# main.net
KiCad netlist of a schematic drawn in EAGLE
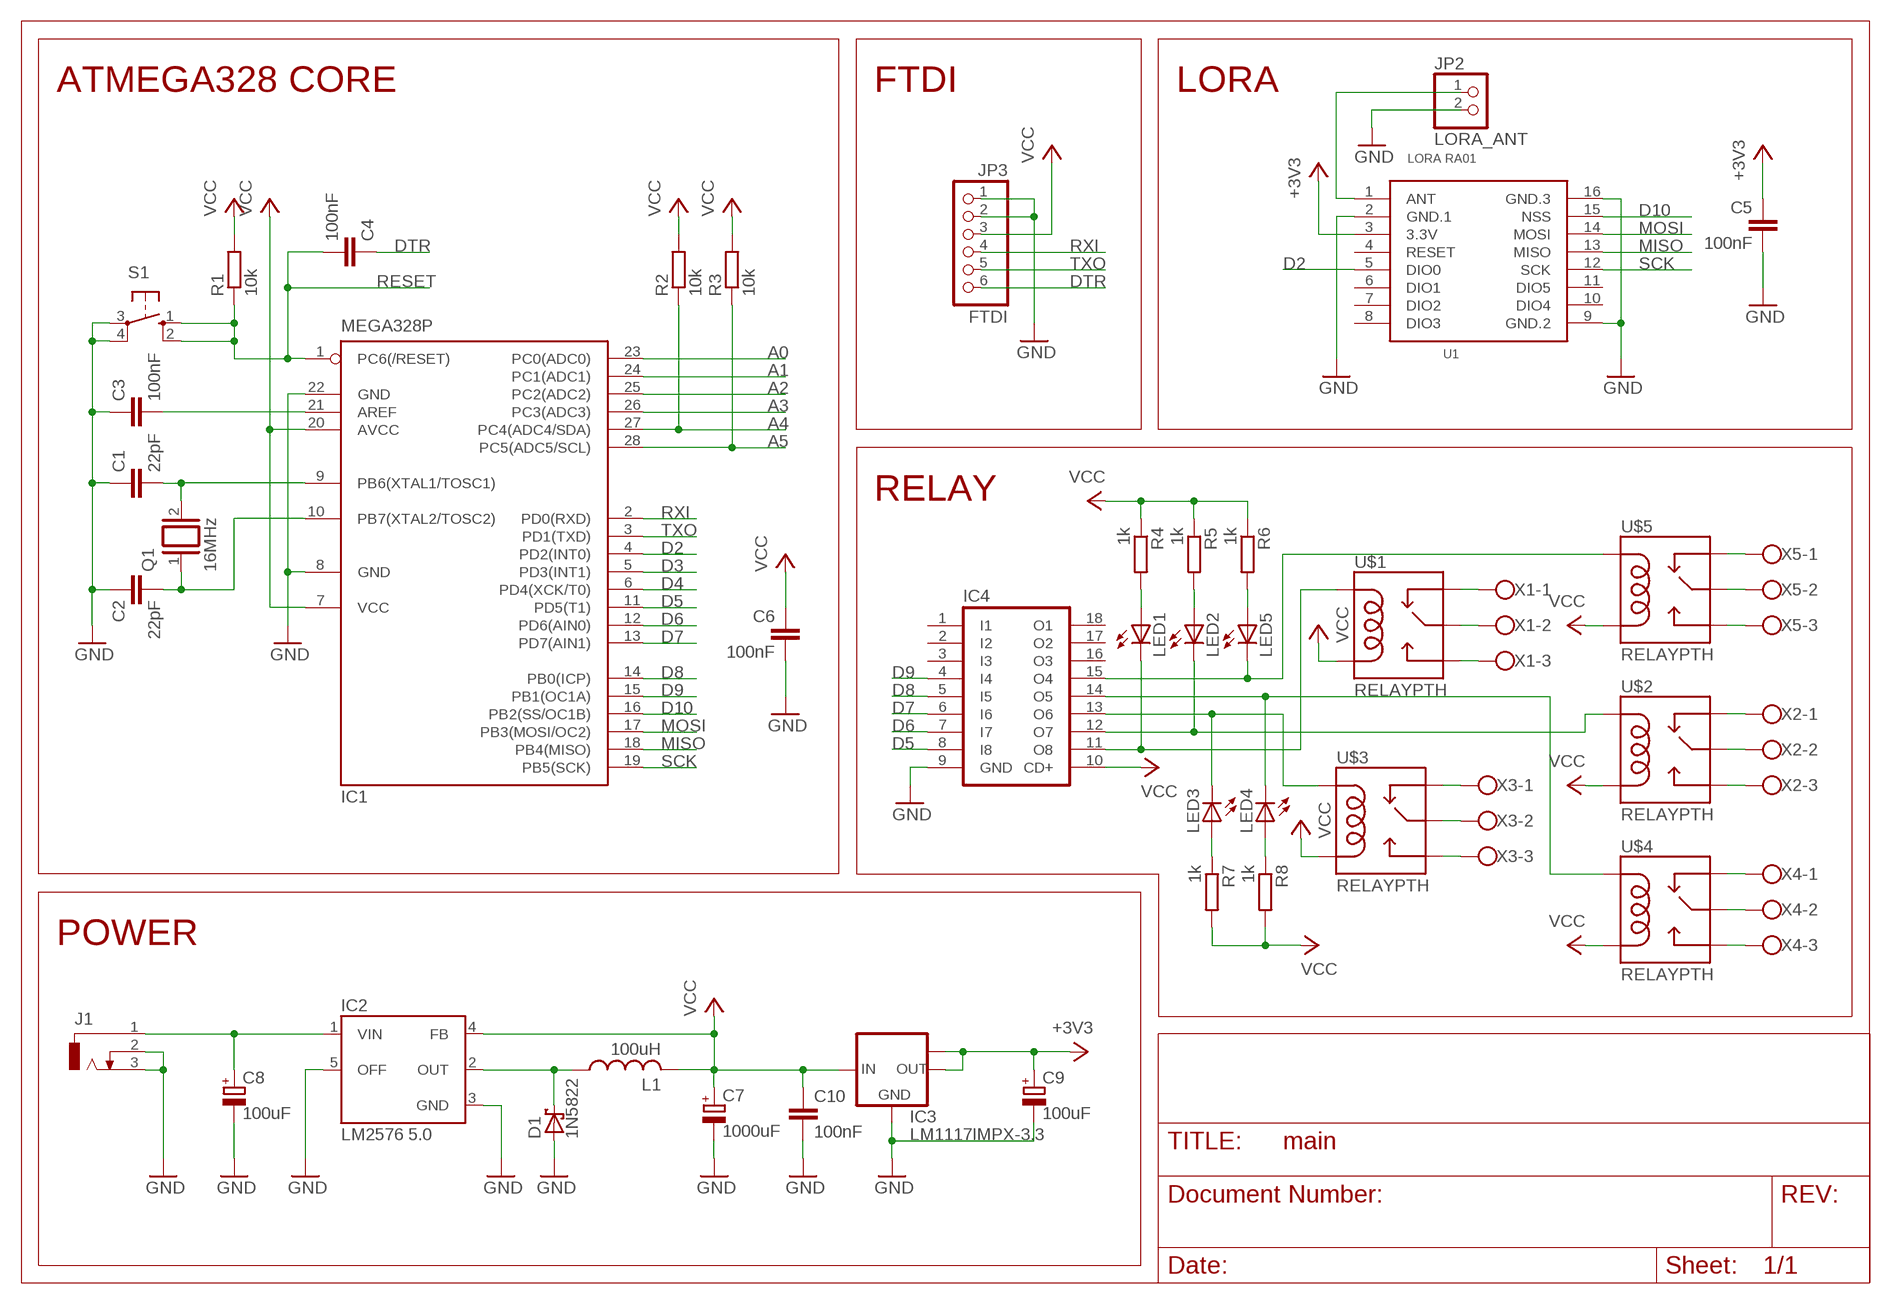
[diagram p0: schematic, sheet 1]

(export (version "E")
  (design (tool "Eeschema 10.0.6"))
  (components
    (comp (ref "C1")
      (value "22pF")
      (footprint "eagle-import:C050-024X044")
      (libsource (lib "eagle-import") (part "C-EU050-024X044"))
    )
    (comp (ref "C2")
      (value "22pF")
      (footprint "eagle-import:C050-024X044")
      (libsource (lib "eagle-import") (part "C-EU050-024X044"))
    )
    (comp (ref "C3")
      (value "100nF")
      (footprint "eagle-import:C050-024X044")
      (libsource (lib "eagle-import") (part "C-EU050-024X044"))
    )
    (comp (ref "C4")
      (value "100nF")
      (footprint "eagle-import:C050-024X044")
      (libsource (lib "eagle-import") (part "C-EU050-024X044"))
    )
    (comp (ref "C5")
      (value "100nF")
      (footprint "eagle-import:C050-024X044")
      (libsource (lib "eagle-import") (part "C-EU050-024X044"))
    )
    (comp (ref "C6")
      (value "100nF")
      (footprint "eagle-import:C050-024X044")
      (libsource (lib "eagle-import") (part "C-EU050-024X044"))
    )
    (comp (ref "C7")
      (value "1000uF")
      (footprint "eagle-import:E5-13")
      (libsource (lib "eagle-import") (part "CPOL-EUE5-13"))
    )
    (comp (ref "C8")
      (value "100uF")
      (footprint "eagle-import:E5-8,5")
      (libsource (lib "eagle-import") (part "CPOL-EUE5-8.5"))
    )
    (comp (ref "C9")
      (value "100uF")
      (footprint "eagle-import:E3,5-10")
      (libsource (lib "eagle-import") (part "CPOL-EUE3.5-10"))
    )
    (comp (ref "C10")
      (value "100nF")
      (footprint "eagle-import:C050-024X044")
      (libsource (lib "eagle-import") (part "C-EU050-024X044"))
    )
    (comp (ref "D1")
      (value "1N5822")
      (footprint "eagle-import:DO201T15")
      (libsource (lib "eagle-import") (part "SCHOTTKY-DIODEDO201T15"))
    )
    (comp (ref "IC1")
      (value "MEGA328P")
      (footprint "eagle-import:DIL28-3")
      (libsource (lib "eagle-import") (part "MEGA8-P"))
    )
    (comp (ref "IC2")
      (value "LM2576 5.0")
      (footprint "eagle-import:TO263-5")
      (libsource (lib "eagle-import") (part "LM2576S"))
    )
    (comp (ref "IC3")
      (value "LM1117IMPX-3.3")
      (footprint "eagle-import:SOT223")
      (libsource (lib "eagle-import") (part "LM1117IMPX-3.3"))
    )
    (comp (ref "IC4")
      (value "ULN2803A")
      (footprint "eagle-import:DIL18")
      (libsource (lib "eagle-import") (part "ULN2803A"))
    )
    (comp (ref "J1")
      (value "DCJ0303")
      (footprint "eagle-import:DCJ0303")
      (libsource (lib "eagle-import") (part "DCJ0303"))
    )
    (comp (ref "JP2")
      (value "LORA_ANT")
      (footprint "eagle-import:1X02")
      (libsource (lib "eagle-import") (part "PINHD-1X2"))
    )
    (comp (ref "JP3")
      (value "FTDI")
      (footprint "eagle-import:1X06")
      (libsource (lib "eagle-import") (part "PINHD-1X6"))
    )
    (comp (ref "L1")
      (value "100uH")
      (footprint "eagle-import:6000-XXXX-RC")
      (libsource (lib "eagle-import") (part "L-US6000-XXX-RC"))
    )
    (comp (ref "LED1")
      (value "LED3MM")
      (footprint "eagle-import:LED3MM")
      (libsource (lib "eagle-import") (part "LED3MM"))
    )
    (comp (ref "LED2")
      (value "LED3MM")
      (footprint "eagle-import:LED3MM")
      (libsource (lib "eagle-import") (part "LED3MM"))
    )
    (comp (ref "LED3")
      (value "LED3MM")
      (footprint "eagle-import:LED3MM")
      (libsource (lib "eagle-import") (part "LED3MM"))
    )
    (comp (ref "LED4")
      (value "LED3MM")
      (footprint "eagle-import:LED3MM")
      (libsource (lib "eagle-import") (part "LED3MM"))
    )
    (comp (ref "LED5")
      (value "LED3MM")
      (footprint "eagle-import:LED3MM")
      (libsource (lib "eagle-import") (part "LED3MM"))
    )
    (comp (ref "Q1")
      (value "16MHz")
      (footprint "eagle-import:QS")
      (libsource (lib "eagle-import") (part "XTAL/S"))
    )
    (comp (ref "R1")
      (value "10k")
      (footprint "eagle-import:0207_10")
      (libsource (lib "eagle-import") (part "R-EU_0207/10"))
    )
    (comp (ref "R2")
      (value "10k")
      (footprint "eagle-import:0207_10")
      (libsource (lib "eagle-import") (part "R-EU_0207/10"))
    )
    (comp (ref "R3")
      (value "10k")
      (footprint "eagle-import:0207_10")
      (libsource (lib "eagle-import") (part "R-EU_0207/10"))
    )
    (comp (ref "R4")
      (value "1k")
      (footprint "eagle-import:0207_10")
      (libsource (lib "eagle-import") (part "R-EU_0207/10"))
    )
    (comp (ref "R5")
      (value "1k")
      (footprint "eagle-import:0207_10")
      (libsource (lib "eagle-import") (part "R-EU_0207/10"))
    )
    (comp (ref "R6")
      (value "1k")
      (footprint "eagle-import:0207_10")
      (libsource (lib "eagle-import") (part "R-EU_0207/10"))
    )
    (comp (ref "R7")
      (value "1k")
      (footprint "eagle-import:0207_10")
      (libsource (lib "eagle-import") (part "R-EU_0207/10"))
    )
    (comp (ref "R8")
      (value "1k")
      (footprint "eagle-import:0207_10")
      (libsource (lib "eagle-import") (part "R-EU_0207/10"))
    )
    (comp (ref "S1")
      (value "10-XX")
      (footprint "eagle-import:B3F-10XX")
      (fields (field (name "MPN") "B3F-1000"))
      (libsource (lib "eagle-import") (part "10-XX"))
    )
    (comp (ref "U$1")
      (value "RELAYPTH")
      (footprint "eagle-import:SRD-05VDC-SL-C")
      (libsource (lib "eagle-import") (part "RELAYPTH"))
    )
    (comp (ref "U$2")
      (value "RELAYPTH")
      (footprint "eagle-import:SRD-05VDC-SL-C")
      (libsource (lib "eagle-import") (part "RELAYPTH"))
    )
    (comp (ref "U$3")
      (value "RELAYPTH")
      (footprint "eagle-import:SRD-05VDC-SL-C")
      (libsource (lib "eagle-import") (part "RELAYPTH"))
    )
    (comp (ref "U$4")
      (value "RELAYPTH")
      (footprint "eagle-import:SRD-05VDC-SL-C")
      (libsource (lib "eagle-import") (part "RELAYPTH"))
    )
    (comp (ref "U$5")
      (value "RELAYPTH")
      (footprint "eagle-import:SRD-05VDC-SL-C")
      (libsource (lib "eagle-import") (part "RELAYPTH"))
    )
    (comp (ref "U1")
      (value "LORA RA01")
      (footprint "eagle-import:LORA-RA1-SMD")
      (libsource (lib "eagle-import") (part "LORA-RA-01-433MHZ"))
    )
    (comp (ref "X1")
      (value "W237-103")
      (footprint "eagle-import:W237-103")
      (fields (field (name "MPN") "237-103"))
      (libsource (lib "eagle-import") (part "W237-103"))
    )
    (comp (ref "X2")
      (value "W237-103")
      (footprint "eagle-import:W237-103")
      (fields (field (name "MPN") "237-103"))
      (libsource (lib "eagle-import") (part "W237-103"))
    )
    (comp (ref "X3")
      (value "W237-103")
      (footprint "eagle-import:W237-103")
      (fields (field (name "MPN") "237-103"))
      (libsource (lib "eagle-import") (part "W237-103"))
    )
    (comp (ref "X4")
      (value "W237-103")
      (footprint "eagle-import:W237-103")
      (fields (field (name "MPN") "237-103"))
      (libsource (lib "eagle-import") (part "W237-103"))
    )
    (comp (ref "X5")
      (value "W237-103")
      (footprint "eagle-import:W237-103")
      (fields (field (name "MPN") "237-103"))
      (libsource (lib "eagle-import") (part "W237-103"))
    )
  )
  (nets
    (net (code "1") (name "+3V3") (class "Default")
      (node (ref "C5") (pin "1") (pinfunction "1_1") (pintype "passive"))
      (node (ref "C9") (pin "+") (pinfunction "+_+") (pintype "passive"))
      (node (ref "IC3") (pin "2") (pinfunction "OUT_2") (pintype "passive"))
      (node (ref "IC3") (pin "TAB") (pinfunction "OUT1_TAB") (pintype "passive"))
      (node (ref "U1") (pin "3") (pinfunction "3.3V_3") (pintype "power_in"))
    )
    (net (code "2") (name "/A0") (class "Default")
      (node (ref "IC1") (pin "23") (pinfunction "PC0(ADC0)_23") (pintype "bidirectional"))
    )
    (net (code "3") (name "/A1") (class "Default")
      (node (ref "IC1") (pin "24") (pinfunction "PC1(ADC1)_24") (pintype "bidirectional"))
    )
    (net (code "4") (name "/A2") (class "Default")
      (node (ref "IC1") (pin "25") (pinfunction "PC2(ADC2)_25") (pintype "bidirectional"))
    )
    (net (code "5") (name "/A3") (class "Default")
      (node (ref "IC1") (pin "26") (pinfunction "PC3(ADC3)_26") (pintype "bidirectional"))
    )
    (net (code "6") (name "/A4") (class "Default")
      (node (ref "IC1") (pin "27") (pinfunction "PC4(ADC4/SDA)_27") (pintype "bidirectional"))
      (node (ref "R2") (pin "1") (pinfunction "1_1") (pintype "passive"))
    )
    (net (code "7") (name "/A5") (class "Default")
      (node (ref "IC1") (pin "28") (pinfunction "PC5(ADC5/SCL)_28") (pintype "bidirectional"))
      (node (ref "R3") (pin "1") (pinfunction "1_1") (pintype "passive"))
    )
    (net (code "8") (name "/D2") (class "Default")
      (node (ref "IC1") (pin "4") (pinfunction "PD2(INT0)_4") (pintype "bidirectional"))
      (node (ref "U1") (pin "5") (pinfunction "DIO0_5") (pintype "bidirectional"))
    )
    (net (code "9") (name "/D3") (class "Default")
      (node (ref "IC1") (pin "5") (pinfunction "PD3(INT1)_5") (pintype "bidirectional"))
    )
    (net (code "10") (name "/D4") (class "Default")
      (node (ref "IC1") (pin "6") (pinfunction "PD4(XCK/T0)_6") (pintype "bidirectional"))
    )
    (net (code "11") (name "/D5") (class "Default")
      (node (ref "IC1") (pin "11") (pinfunction "PD5(T1)_11") (pintype "bidirectional"))
      (node (ref "IC4") (pin "8") (pinfunction "I8_8") (pintype "input"))
    )
    (net (code "12") (name "/D6") (class "Default")
      (node (ref "IC1") (pin "12") (pinfunction "PD6(AIN0)_12") (pintype "bidirectional"))
      (node (ref "IC4") (pin "7") (pinfunction "I7_7") (pintype "input"))
    )
    (net (code "13") (name "/D7") (class "Default")
      (node (ref "IC1") (pin "13") (pinfunction "PD7(AIN1)_13") (pintype "bidirectional"))
      (node (ref "IC4") (pin "6") (pinfunction "I6_6") (pintype "input"))
    )
    (net (code "14") (name "/D8") (class "Default")
      (node (ref "IC1") (pin "14") (pinfunction "PB0(ICP)_14") (pintype "bidirectional"))
      (node (ref "IC4") (pin "5") (pinfunction "I5_5") (pintype "input"))
    )
    (net (code "15") (name "/D9") (class "Default")
      (node (ref "IC1") (pin "15") (pinfunction "PB1(OC1A)_15") (pintype "bidirectional"))
      (node (ref "IC4") (pin "4") (pinfunction "I4_4") (pintype "input"))
    )
    (net (code "16") (name "/D10") (class "Default")
      (node (ref "IC1") (pin "16") (pinfunction "PB2(SS/OC1B)_16") (pintype "bidirectional"))
      (node (ref "U1") (pin "15") (pinfunction "NSS_15") (pintype "bidirectional"))
    )
    (net (code "17") (name "/DTR") (class "Default")
      (node (ref "C4") (pin "1") (pinfunction "1_1") (pintype "passive"))
      (node (ref "JP3") (pin "6") (pinfunction "6_6") (pintype "passive"))
    )
    (net (code "18") (name "/MISO") (class "Default")
      (node (ref "IC1") (pin "18") (pinfunction "PB4(MISO)_18") (pintype "bidirectional"))
      (node (ref "U1") (pin "13") (pinfunction "MISO_13") (pintype "bidirectional"))
    )
    (net (code "19") (name "/MOSI") (class "Default")
      (node (ref "IC1") (pin "17") (pinfunction "PB3(MOSI/OC2)_17") (pintype "bidirectional"))
      (node (ref "U1") (pin "14") (pinfunction "MOSI_14") (pintype "bidirectional"))
    )
    (net (code "20") (name "/RESET") (class "Default")
      (node (ref "C4") (pin "2") (pinfunction "2_2") (pintype "passive"))
      (node (ref "IC1") (pin "1") (pinfunction "PC6(/RESET)_1") (pintype "bidirectional"))
      (node (ref "R1") (pin "1") (pinfunction "1_1") (pintype "passive"))
      (node (ref "S1") (pin "1") (pinfunction "S_1") (pintype "passive"))
      (node (ref "S1") (pin "2") (pinfunction "S1_2") (pintype "passive"))
    )
    (net (code "21") (name "/RXI") (class "Default")
      (node (ref "IC1") (pin "2") (pinfunction "PD0(RXD)_2") (pintype "bidirectional"))
      (node (ref "JP3") (pin "4") (pinfunction "4_4") (pintype "passive"))
    )
    (net (code "22") (name "/SCK") (class "Default")
      (node (ref "IC1") (pin "19") (pinfunction "PB5(SCK)_19") (pintype "bidirectional"))
      (node (ref "U1") (pin "12") (pinfunction "SCK_12") (pintype "bidirectional"))
    )
    (net (code "23") (name "/TXO") (class "Default")
      (node (ref "IC1") (pin "3") (pinfunction "PD1(TXD)_3") (pintype "bidirectional"))
      (node (ref "JP3") (pin "5") (pinfunction "5_5") (pintype "passive"))
    )
    (net (code "24") (name "GND") (class "Default")
      (node (ref "C1") (pin "1") (pinfunction "1_1") (pintype "passive"))
      (node (ref "C10") (pin "2") (pinfunction "2_2") (pintype "passive"))
      (node (ref "C2") (pin "1") (pinfunction "1_1") (pintype "passive"))
      (node (ref "C3") (pin "1") (pinfunction "1_1") (pintype "passive"))
      (node (ref "C5") (pin "2") (pinfunction "2_2") (pintype "passive"))
      (node (ref "C6") (pin "2") (pinfunction "2_2") (pintype "passive"))
      (node (ref "C7") (pin "-") (pinfunction "-_-") (pintype "passive"))
      (node (ref "C8") (pin "-") (pinfunction "-_-") (pintype "passive"))
      (node (ref "C9") (pin "-") (pinfunction "-_-") (pintype "passive"))
      (node (ref "D1") (pin "A") (pinfunction "A_A") (pintype "passive"))
      (node (ref "IC1") (pin "22") (pinfunction "GND_22") (pintype "power_in"))
      (node (ref "IC1") (pin "8") (pinfunction "GND_8") (pintype "power_in"))
      (node (ref "IC2") (pin "3") (pinfunction "GND_3") (pintype "power_in"))
      (node (ref "IC2") (pin "5") (pinfunction "OFF_5") (pintype "input"))
      (node (ref "IC3") (pin "1") (pinfunction "GND_1") (pintype "input"))
      (node (ref "IC4") (pin "9") (pinfunction "GND_9") (pintype "power_in"))
      (node (ref "J1") (pin "2") (pinfunction "2_2") (pintype "passive"))
      (node (ref "J1") (pin "3") (pinfunction "3_3") (pintype "passive"))
      (node (ref "JP2") (pin "2") (pinfunction "2_2") (pintype "passive"))
      (node (ref "JP3") (pin "1") (pinfunction "1_1") (pintype "passive"))
      (node (ref "JP3") (pin "2") (pinfunction "2_2") (pintype "passive"))
      (node (ref "S1") (pin "3") (pinfunction "P_3") (pintype "passive"))
      (node (ref "S1") (pin "4") (pinfunction "P1_4") (pintype "passive"))
      (node (ref "U1") (pin "16") (pinfunction "GND.3_16") (pintype "power_in"))
      (node (ref "U1") (pin "2") (pinfunction "GND.1_2") (pintype "power_in"))
      (node (ref "U1") (pin "9") (pinfunction "GND.2_9") (pintype "power_in"))
    )
    (net (code "25") (name "Net-(IC1-AREF)") (class "Default")
      (node (ref "C3") (pin "2") (pinfunction "2_2") (pintype "passive"))
      (node (ref "IC1") (pin "21") (pinfunction "AREF_21") (pintype "passive"))
    )
    (net (code "26") (name "Net-(IC1-PB6(XTAL1{slash}TOSC1))") (class "Default")
      (node (ref "C1") (pin "2") (pinfunction "2_2") (pintype "passive"))
      (node (ref "IC1") (pin "9") (pinfunction "PB6(XTAL1/TOSC1)_9") (pintype "bidirectional"))
      (node (ref "Q1") (pin "2") (pinfunction "2_2") (pintype "passive"))
    )
    (net (code "27") (name "Net-(IC1-PB7(XTAL2{slash}TOSC2))") (class "Default")
      (node (ref "C2") (pin "2") (pinfunction "2_2") (pintype "passive"))
      (node (ref "IC1") (pin "10") (pinfunction "PB7(XTAL2/TOSC2)_10") (pintype "bidirectional"))
      (node (ref "Q1") (pin "1") (pinfunction "1_1") (pintype "passive"))
    )
    (net (code "28") (name "Net-(IC2-OUT)") (class "Default")
      (node (ref "D1") (pin "C") (pinfunction "C_C") (pintype "passive"))
      (node (ref "IC2") (pin "2") (pinfunction "OUT_2") (pintype "output"))
      (node (ref "L1") (pin "1") (pinfunction "1_1") (pintype "passive"))
    )
    (net (code "29") (name "Net-(IC2-VIN)") (class "Default")
      (node (ref "C8") (pin "+") (pinfunction "+_+") (pintype "passive"))
      (node (ref "IC2") (pin "1") (pinfunction "VIN_1") (pintype "power_in"))
      (node (ref "J1") (pin "1") (pinfunction "1_1") (pintype "passive"))
    )
    (net (code "30") (name "Net-(IC4-O4)") (class "Default")
      (node (ref "IC4") (pin "15") (pinfunction "O4_15") (pintype "open_collector"))
      (node (ref "LED5") (pin "K") (pinfunction "C_K") (pintype "passive"))
      (node (ref "U$5") (pin "COIL1") (pinfunction "COIL1_COIL1") (pintype "bidirectional"))
    )
    (net (code "31") (name "Net-(IC4-O5)") (class "Default")
      (node (ref "IC4") (pin "14") (pinfunction "O5_14") (pintype "open_collector"))
      (node (ref "LED4") (pin "K") (pinfunction "C_K") (pintype "passive"))
      (node (ref "U$4") (pin "COIL1") (pinfunction "COIL1_COIL1") (pintype "bidirectional"))
    )
    (net (code "32") (name "Net-(IC4-O6)") (class "Default")
      (node (ref "IC4") (pin "13") (pinfunction "O6_13") (pintype "open_collector"))
      (node (ref "LED3") (pin "K") (pinfunction "C_K") (pintype "passive"))
      (node (ref "U$3") (pin "COIL1") (pinfunction "COIL1_COIL1") (pintype "bidirectional"))
    )
    (net (code "33") (name "Net-(IC4-O7)") (class "Default")
      (node (ref "IC4") (pin "12") (pinfunction "O7_12") (pintype "open_collector"))
      (node (ref "LED2") (pin "K") (pinfunction "C_K") (pintype "passive"))
      (node (ref "U$2") (pin "COIL1") (pinfunction "COIL1_COIL1") (pintype "bidirectional"))
    )
    (net (code "34") (name "Net-(IC4-O8)") (class "Default")
      (node (ref "IC4") (pin "11") (pinfunction "O8_11") (pintype "open_collector"))
      (node (ref "LED1") (pin "K") (pinfunction "C_K") (pintype "passive"))
      (node (ref "U$1") (pin "COIL1") (pinfunction "COIL1_COIL1") (pintype "bidirectional"))
    )
    (net (code "35") (name "Net-(LED1-PadA)") (class "Default")
      (node (ref "LED1") (pin "A") (pinfunction "A_A") (pintype "passive"))
      (node (ref "R4") (pin "2") (pinfunction "2_2") (pintype "passive"))
    )
    (net (code "36") (name "Net-(LED2-PadA)") (class "Default")
      (node (ref "LED2") (pin "A") (pinfunction "A_A") (pintype "passive"))
      (node (ref "R5") (pin "2") (pinfunction "2_2") (pintype "passive"))
    )
    (net (code "37") (name "Net-(LED3-PadA)") (class "Default")
      (node (ref "LED3") (pin "A") (pinfunction "A_A") (pintype "passive"))
      (node (ref "R7") (pin "1") (pinfunction "1_1") (pintype "passive"))
    )
    (net (code "38") (name "Net-(LED4-PadA)") (class "Default")
      (node (ref "LED4") (pin "A") (pinfunction "A_A") (pintype "passive"))
      (node (ref "R8") (pin "1") (pinfunction "1_1") (pintype "passive"))
    )
    (net (code "39") (name "Net-(LED5-PadA)") (class "Default")
      (node (ref "LED5") (pin "A") (pinfunction "A_A") (pintype "passive"))
      (node (ref "R6") (pin "2") (pinfunction "2_2") (pintype "passive"))
    )
    (net (code "40") (name "Net-(U$1-SWCLOSE)") (class "Default")
      (node (ref "U$1") (pin "SWCLOSED") (pinfunction "SWCLOSE_SWCLOSED") (pintype "bidirectional"))
      (node (ref "X1") (pin "1") (pinfunction "KL_1") (pintype "passive"))
    )
    (net (code "41") (name "Net-(U$2-SWCLOSE)") (class "Default")
      (node (ref "U$2") (pin "SWCLOSED") (pinfunction "SWCLOSE_SWCLOSED") (pintype "bidirectional"))
      (node (ref "X2") (pin "1") (pinfunction "KL_1") (pintype "passive"))
    )
    (net (code "42") (name "Net-(U$3-SWCLOSE)") (class "Default")
      (node (ref "U$3") (pin "SWCLOSED") (pinfunction "SWCLOSE_SWCLOSED") (pintype "bidirectional"))
      (node (ref "X3") (pin "1") (pinfunction "KL_1") (pintype "passive"))
    )
    (net (code "43") (name "Net-(U$4-SWCLOSE)") (class "Default")
      (node (ref "U$4") (pin "SWCLOSED") (pinfunction "SWCLOSE_SWCLOSED") (pintype "bidirectional"))
      (node (ref "X4") (pin "1") (pinfunction "KL_1") (pintype "passive"))
    )
    (net (code "44") (name "Net-(U$5-SWCLOSE)") (class "Default")
      (node (ref "U$5") (pin "SWCLOSED") (pinfunction "SWCLOSE_SWCLOSED") (pintype "bidirectional"))
      (node (ref "X5") (pin "1") (pinfunction "KL_1") (pintype "passive"))
    )
    (net (code "45") (name "Net-(U1-ANT)") (class "Default")
      (node (ref "JP2") (pin "1") (pinfunction "1_1") (pintype "passive"))
      (node (ref "U1") (pin "1") (pinfunction "ANT_1") (pintype "bidirectional"))
    )
    (net (code "46") (name "Net-(X1B-KL)") (class "Default")
      (node (ref "U$1") (pin "SWCOMMON") (pinfunction "SWCOMMON_SWCOMMON") (pintype "bidirectional"))
      (node (ref "X1") (pin "2") (pinfunction "KL_2") (pintype "passive"))
    )
    (net (code "47") (name "Net-(X1C-KL)") (class "Default")
      (node (ref "U$1") (pin "SWOPEN") (pinfunction "SWOPEN_SWOPEN") (pintype "bidirectional"))
      (node (ref "X1") (pin "3") (pinfunction "KL_3") (pintype "passive"))
    )
    (net (code "48") (name "Net-(X2B-KL)") (class "Default")
      (node (ref "U$2") (pin "SWCOMMON") (pinfunction "SWCOMMON_SWCOMMON") (pintype "bidirectional"))
      (node (ref "X2") (pin "2") (pinfunction "KL_2") (pintype "passive"))
    )
    (net (code "49") (name "Net-(X2C-KL)") (class "Default")
      (node (ref "U$2") (pin "SWOPEN") (pinfunction "SWOPEN_SWOPEN") (pintype "bidirectional"))
      (node (ref "X2") (pin "3") (pinfunction "KL_3") (pintype "passive"))
    )
    (net (code "50") (name "Net-(X3B-KL)") (class "Default")
      (node (ref "U$3") (pin "SWCOMMON") (pinfunction "SWCOMMON_SWCOMMON") (pintype "bidirectional"))
      (node (ref "X3") (pin "2") (pinfunction "KL_2") (pintype "passive"))
    )
    (net (code "51") (name "Net-(X3C-KL)") (class "Default")
      (node (ref "U$3") (pin "SWOPEN") (pinfunction "SWOPEN_SWOPEN") (pintype "bidirectional"))
      (node (ref "X3") (pin "3") (pinfunction "KL_3") (pintype "passive"))
    )
    (net (code "52") (name "Net-(X4B-KL)") (class "Default")
      (node (ref "U$4") (pin "SWCOMMON") (pinfunction "SWCOMMON_SWCOMMON") (pintype "bidirectional"))
      (node (ref "X4") (pin "2") (pinfunction "KL_2") (pintype "passive"))
    )
    (net (code "53") (name "Net-(X4C-KL)") (class "Default")
      (node (ref "U$4") (pin "SWOPEN") (pinfunction "SWOPEN_SWOPEN") (pintype "bidirectional"))
      (node (ref "X4") (pin "3") (pinfunction "KL_3") (pintype "passive"))
    )
    (net (code "54") (name "Net-(X5B-KL)") (class "Default")
      (node (ref "U$5") (pin "SWCOMMON") (pinfunction "SWCOMMON_SWCOMMON") (pintype "bidirectional"))
      (node (ref "X5") (pin "2") (pinfunction "KL_2") (pintype "passive"))
    )
    (net (code "55") (name "Net-(X5C-KL)") (class "Default")
      (node (ref "U$5") (pin "SWOPEN") (pinfunction "SWOPEN_SWOPEN") (pintype "bidirectional"))
      (node (ref "X5") (pin "3") (pinfunction "KL_3") (pintype "passive"))
    )
    (net (code "56") (name "VCC") (class "Default")
      (node (ref "C10") (pin "1") (pinfunction "1_1") (pintype "passive"))
      (node (ref "C6") (pin "1") (pinfunction "1_1") (pintype "passive"))
      (node (ref "C7") (pin "+") (pinfunction "+_+") (pintype "passive"))
      (node (ref "IC1") (pin "20") (pinfunction "AVCC_20") (pintype "power_in"))
      (node (ref "IC1") (pin "7") (pinfunction "VCC_7") (pintype "power_in"))
      (node (ref "IC2") (pin "4") (pinfunction "FB_4") (pintype "input"))
      (node (ref "IC3") (pin "3") (pinfunction "IN_3") (pintype "input"))
      (node (ref "IC4") (pin "10") (pinfunction "CD+_10") (pintype "passive"))
      (node (ref "JP3") (pin "3") (pinfunction "3_3") (pintype "passive"))
      (node (ref "L1") (pin "2") (pinfunction "2_2") (pintype "passive"))
      (node (ref "R1") (pin "2") (pinfunction "2_2") (pintype "passive"))
      (node (ref "R2") (pin "2") (pinfunction "2_2") (pintype "passive"))
      (node (ref "R3") (pin "2") (pinfunction "2_2") (pintype "passive"))
      (node (ref "R4") (pin "1") (pinfunction "1_1") (pintype "passive"))
      (node (ref "R5") (pin "1") (pinfunction "1_1") (pintype "passive"))
      (node (ref "R6") (pin "1") (pinfunction "1_1") (pintype "passive"))
      (node (ref "R7") (pin "2") (pinfunction "2_2") (pintype "passive"))
      (node (ref "R8") (pin "2") (pinfunction "2_2") (pintype "passive"))
      (node (ref "U$1") (pin "COIL0") (pinfunction "COIL0_COIL0") (pintype "bidirectional"))
      (node (ref "U$2") (pin "COIL0") (pinfunction "COIL0_COIL0") (pintype "bidirectional"))
      (node (ref "U$3") (pin "COIL0") (pinfunction "COIL0_COIL0") (pintype "bidirectional"))
      (node (ref "U$4") (pin "COIL0") (pinfunction "COIL0_COIL0") (pintype "bidirectional"))
      (node (ref "U$5") (pin "COIL0") (pinfunction "COIL0_COIL0") (pintype "bidirectional"))
    )
    (net (code "57") (name "unconnected-(IC4-I1-Pad1)") (class "Default")
      (node (ref "IC4") (pin "1") (pinfunction "I1_1") (pintype "input"))
    )
    (net (code "58") (name "unconnected-(IC4-I2-Pad2)") (class "Default")
      (node (ref "IC4") (pin "2") (pinfunction "I2_2") (pintype "input"))
    )
    (net (code "59") (name "unconnected-(IC4-I3-Pad3)") (class "Default")
      (node (ref "IC4") (pin "3") (pinfunction "I3_3") (pintype "input"))
    )
    (net (code "60") (name "unconnected-(IC4-O1-Pad18)") (class "Default")
      (node (ref "IC4") (pin "18") (pinfunction "O1_18") (pintype "open_collector"))
    )
    (net (code "61") (name "unconnected-(IC4-O2-Pad17)") (class "Default")
      (node (ref "IC4") (pin "17") (pinfunction "O2_17") (pintype "open_collector"))
    )
    (net (code "62") (name "unconnected-(IC4-O3-Pad16)") (class "Default")
      (node (ref "IC4") (pin "16") (pinfunction "O3_16") (pintype "open_collector"))
    )
    (net (code "63") (name "unconnected-(U1-DIO1-Pad6)") (class "Default")
      (node (ref "U1") (pin "6") (pinfunction "DIO1_6") (pintype "bidirectional"))
    )
    (net (code "64") (name "unconnected-(U1-DIO2-Pad7)") (class "Default")
      (node (ref "U1") (pin "7") (pinfunction "DIO2_7") (pintype "bidirectional"))
    )
    (net (code "65") (name "unconnected-(U1-DIO3-Pad8)") (class "Default")
      (node (ref "U1") (pin "8") (pinfunction "DIO3_8") (pintype "bidirectional"))
    )
    (net (code "66") (name "unconnected-(U1-DIO4-Pad10)") (class "Default")
      (node (ref "U1") (pin "10") (pinfunction "DIO4_10") (pintype "bidirectional"))
    )
    (net (code "67") (name "unconnected-(U1-DIO5-Pad11)") (class "Default")
      (node (ref "U1") (pin "11") (pinfunction "DIO5_11") (pintype "bidirectional"))
    )
    (net (code "68") (name "unconnected-(U1-RESET-Pad4)") (class "Default")
      (node (ref "U1") (pin "4") (pinfunction "RESET_4") (pintype "bidirectional"))
    )
  )
)
